# uNav44_r1_2.net
KiCad netlist of a schematic drawn in EAGLE
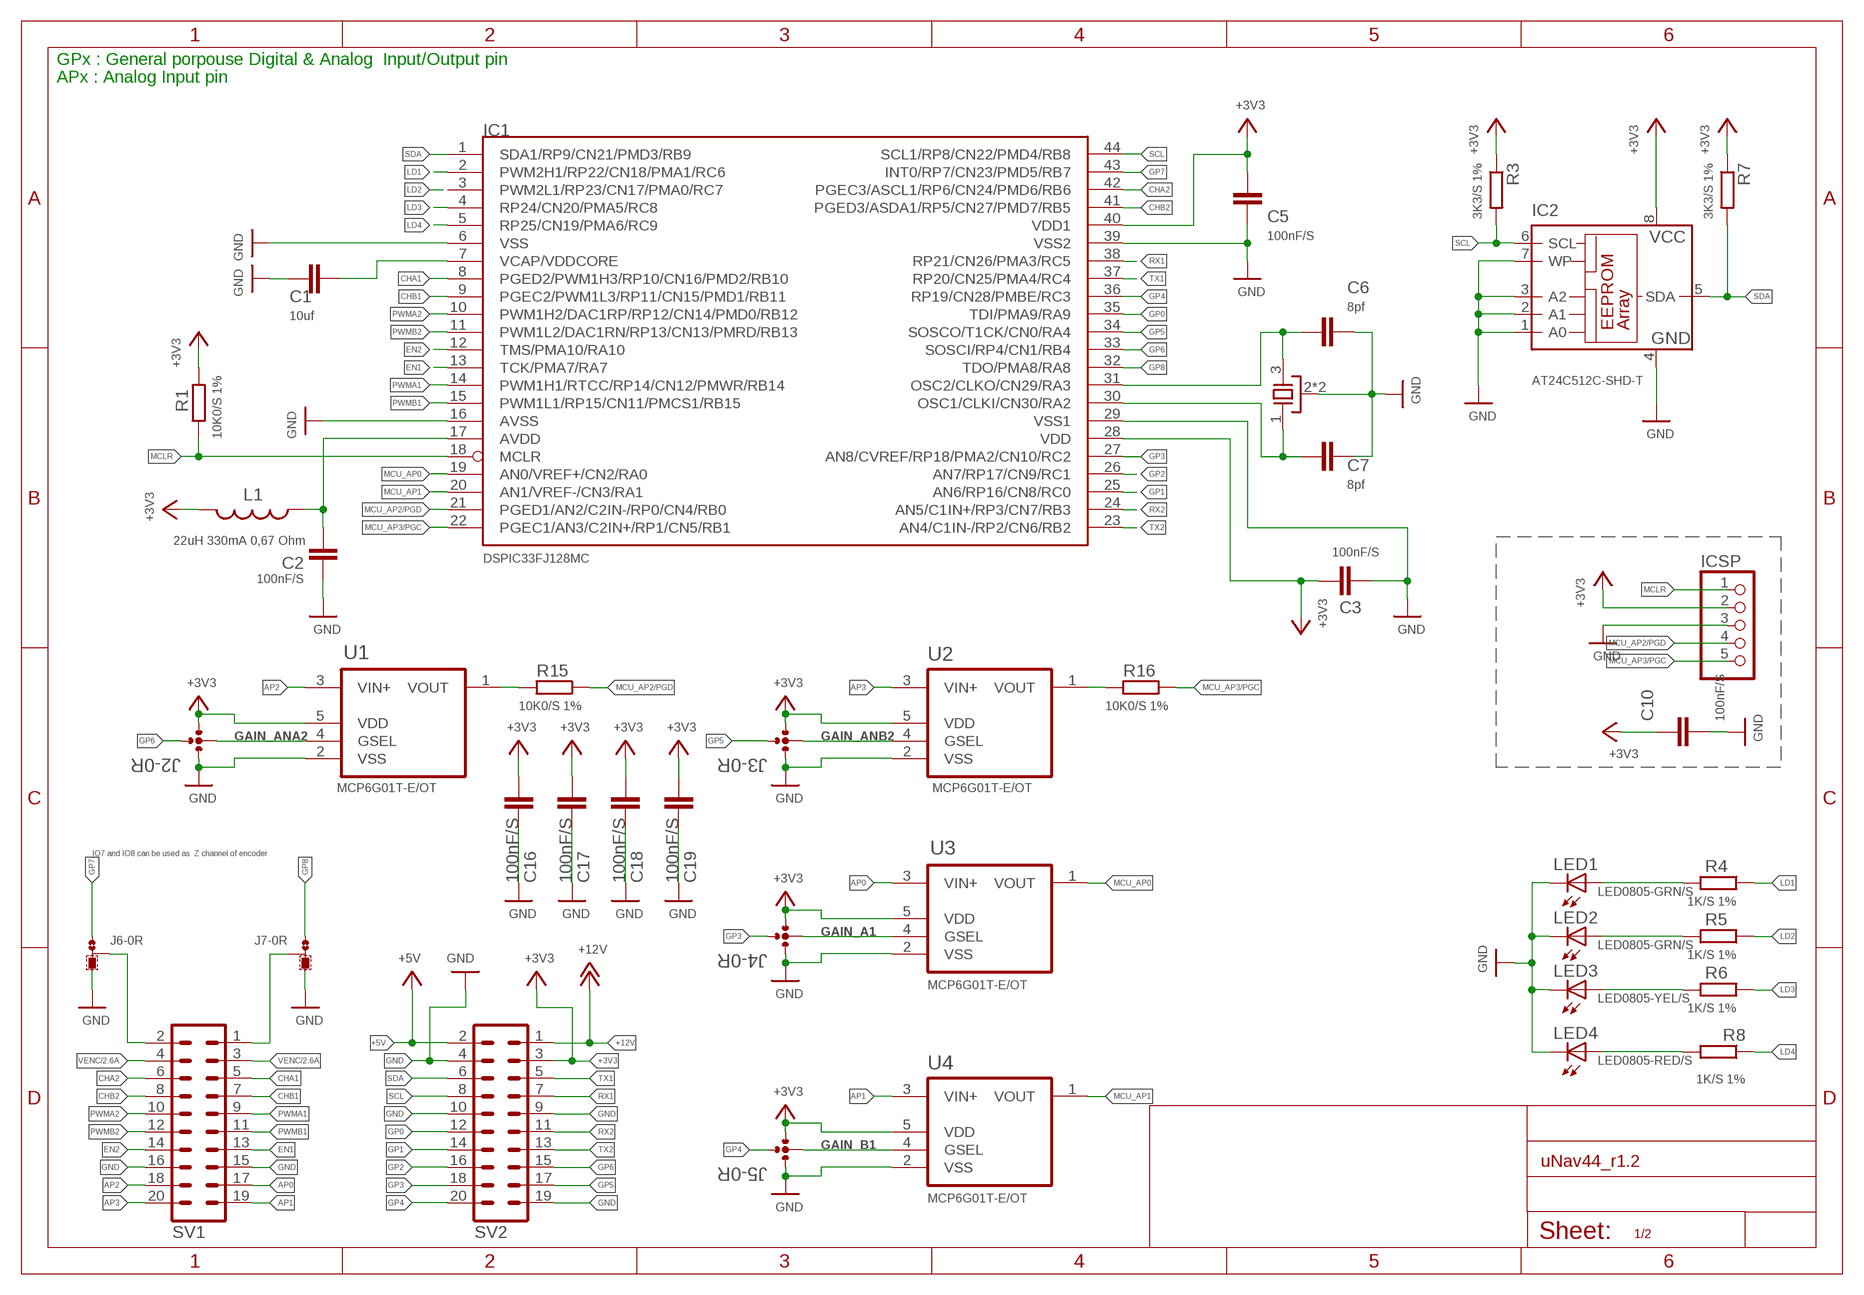
[diagram p0: schematic, sheet 1]
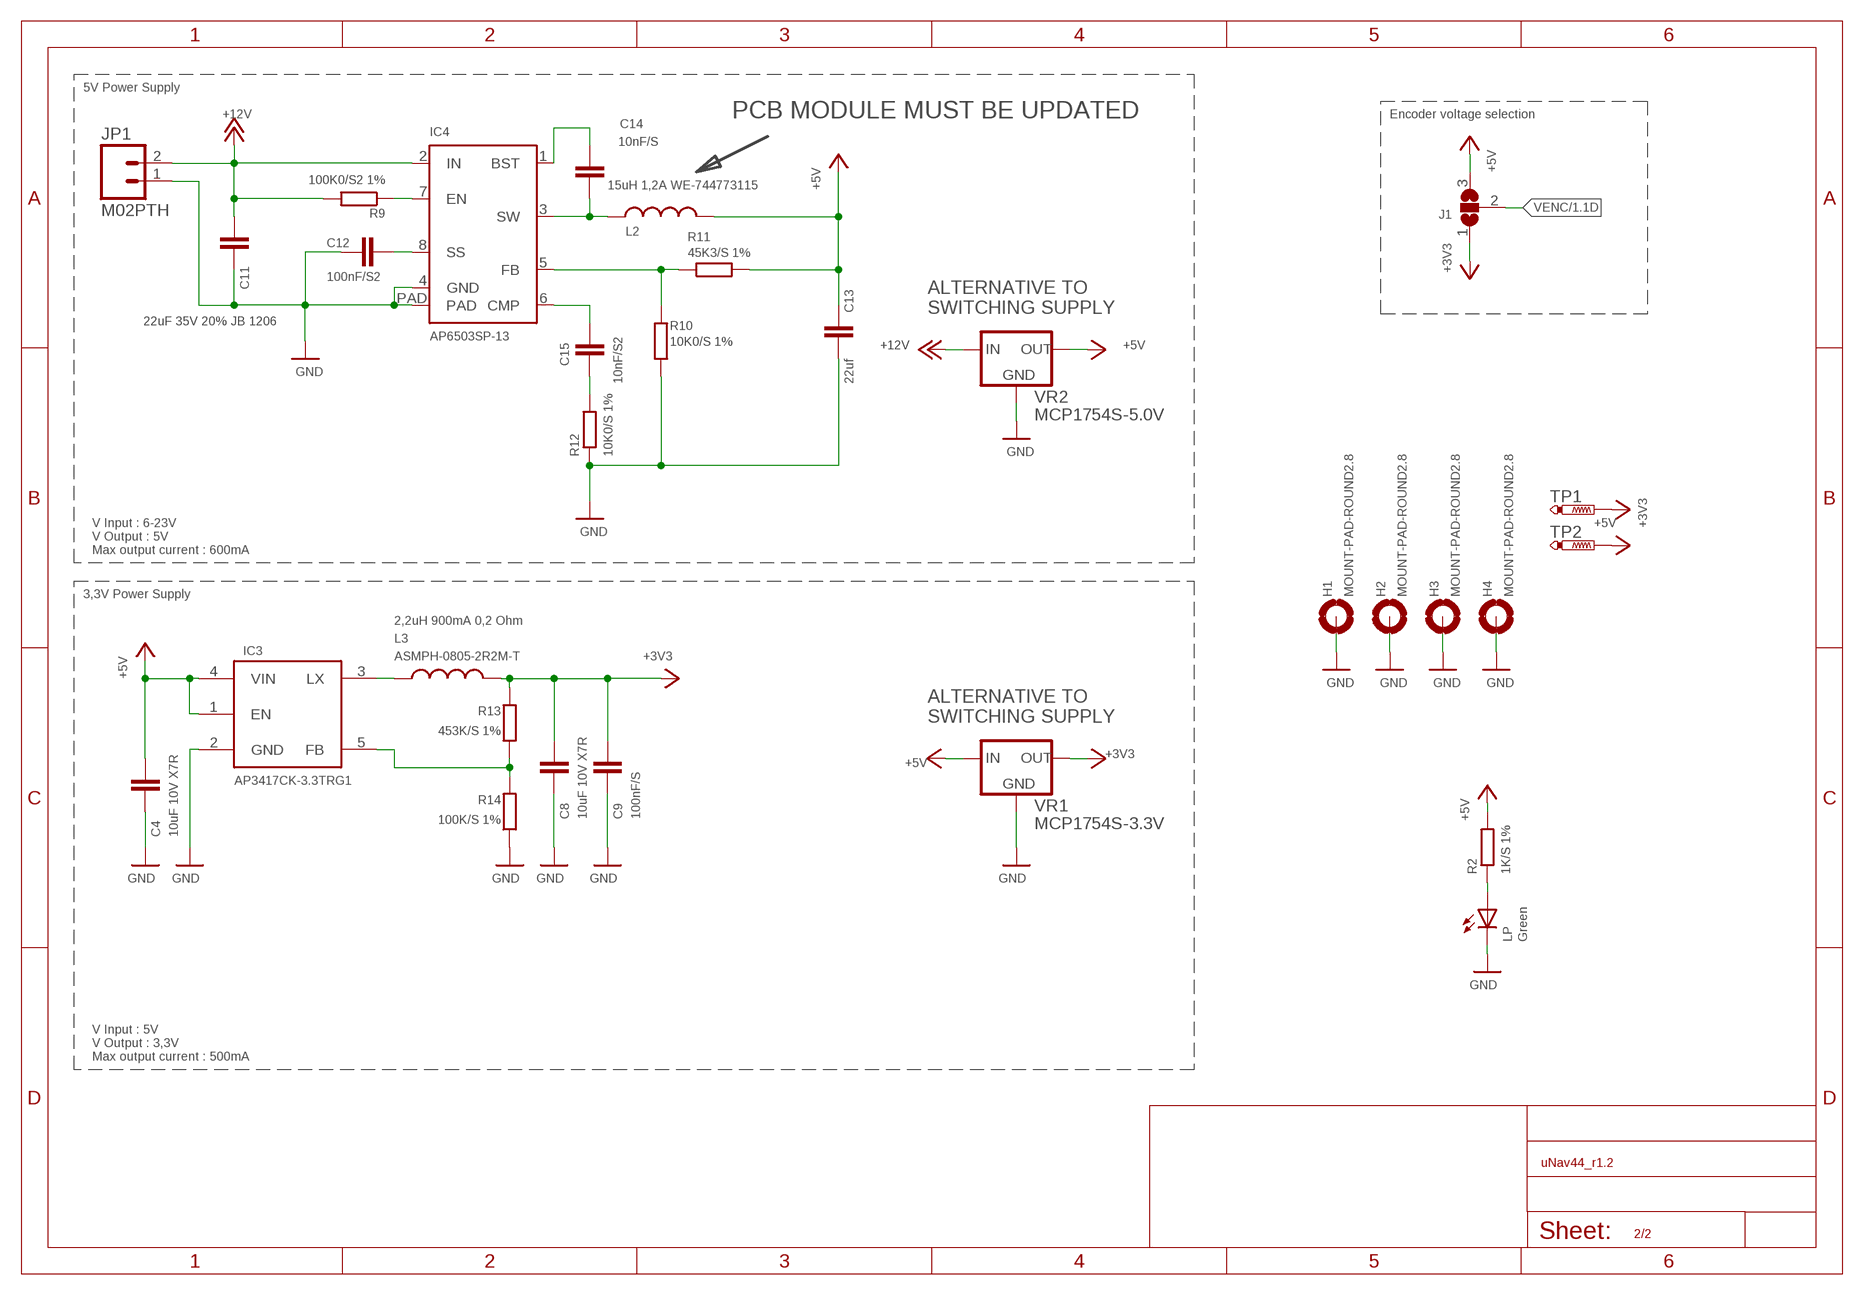
[diagram p1: schematic, sheet 2]

(export (version "E")
  (design (tool "Eeschema 10.0.6"))
  (components
    (comp (ref "C1")
      (value "10uf")
      (footprint "eagle-import:C1206")
      (libsource (lib "eagle-import") (part "C-EUC1206"))
    )
    (comp (ref "C2")
      (value "100nF/S")
      (footprint "eagle-import:C0603")
      (libsource (lib "eagle-import") (part "C-EUC0603"))
    )
    (comp (ref "C3")
      (value "100nF/S")
      (footprint "eagle-import:C0603")
      (libsource (lib "eagle-import") (part "C-EUC0603"))
    )
    (comp (ref "C5")
      (value "100nF/S")
      (footprint "eagle-import:C0603")
      (libsource (lib "eagle-import") (part "C-EUC0603"))
    )
    (comp (ref "C6")
      (value "8pf")
      (footprint "eagle-import:C0603")
      (libsource (lib "eagle-import") (part "C-EUC0603"))
    )
    (comp (ref "C7")
      (value "8pf")
      (footprint "eagle-import:C0603")
      (libsource (lib "eagle-import") (part "C-EUC0603"))
    )
    (comp (ref "C10")
      (value "100nF/S")
      (footprint "eagle-import:C0603")
      (libsource (lib "eagle-import") (part "C-EUC0603"))
    )
    (comp (ref "C16")
      (value "100nF/S")
      (footprint "eagle-import:C0603")
      (libsource (lib "eagle-import") (part "C-EUC0603"))
    )
    (comp (ref "C17")
      (value "100nF/S")
      (footprint "eagle-import:C0603")
      (libsource (lib "eagle-import") (part "C-EUC0603"))
    )
    (comp (ref "C18")
      (value "100nF/S")
      (footprint "eagle-import:C0603")
      (libsource (lib "eagle-import") (part "C-EUC0603"))
    )
    (comp (ref "C19")
      (value "100nF/S")
      (footprint "eagle-import:C0603")
      (libsource (lib "eagle-import") (part "C-EUC0603"))
    )
    (comp (ref "IC1")
      (value "DSPIC33FJ128MC")
      (footprint "eagle-import:TQFP44")
      (libsource (lib "eagle-import") (part "DSPIC33FJ128MC804-PT"))
    )
    (comp (ref "IC2")
      (value "AT24C512C-SHD-T")
      (footprint "eagle-import:SO-08M")
      (libsource (lib "eagle-import") (part "24SMAA01"))
    )
    (comp (ref "ICSP")
      (value "PINHD-1X05_2.54-S")
      (footprint "eagle-import:1X05-S")
      (libsource (lib "eagle-import") (part "PINHD-1X05_2.54-S"))
    )
    (comp (ref "J2")
      (value "0R-JUMP-4")
      (footprint "eagle-import:C0R-JUMP-4")
      (libsource (lib "eagle-import") (part "0R-JUMP-4"))
    )
    (comp (ref "J3")
      (value "0R-JUMP-4")
      (footprint "eagle-import:C0R-JUMP-4")
      (libsource (lib "eagle-import") (part "0R-JUMP-4"))
    )
    (comp (ref "J4")
      (value "0R-JUMP-4")
      (footprint "eagle-import:C0R-JUMP-4")
      (libsource (lib "eagle-import") (part "0R-JUMP-4"))
    )
    (comp (ref "J5")
      (value "0R-JUMP-4")
      (footprint "eagle-import:C0R-JUMP-4")
      (libsource (lib "eagle-import") (part "0R-JUMP-4"))
    )
    (comp (ref "J6")
      (value "0R-JUMPC")
      (footprint "eagle-import:C0R-JMP")
      (libsource (lib "eagle-import") (part "0R-JUMPC"))
    )
    (comp (ref "J7")
      (value "0R-JUMPC")
      (footprint "eagle-import:C0R-JMP")
      (libsource (lib "eagle-import") (part "0R-JUMPC"))
    )
    (comp (ref "L1")
      (value "22uH 330mA 0,67 Ohm")
      (footprint "eagle-import:0805")
      (libsource (lib "eagle-import") (part "INDUCTOR0805"))
    )
    (comp (ref "LED1")
      (value "LED0805-GRN/S")
      (footprint "eagle-import:CHIPLED_0805")
      (libsource (lib "eagle-import") (part "LEDCHIPLED_0805"))
    )
    (comp (ref "LED2")
      (value "LED0805-GRN/S")
      (footprint "eagle-import:CHIPLED_0805")
      (libsource (lib "eagle-import") (part "LEDCHIPLED_0805"))
    )
    (comp (ref "LED3")
      (value "LED0805-YEL/S")
      (footprint "eagle-import:CHIPLED_0805")
      (libsource (lib "eagle-import") (part "LEDCHIPLED_0805"))
    )
    (comp (ref "LED4")
      (value "LED0805-RED/S")
      (footprint "eagle-import:CHIPLED_0805")
      (libsource (lib "eagle-import") (part "LEDCHIPLED_0805"))
    )
    (comp (ref "R1")
      (value "10K0/S 1%")
      (footprint "eagle-import:R0603")
      (libsource (lib "eagle-import") (part "R-EU_R0603"))
    )
    (comp (ref "R3")
      (value "3K3/S 1%")
      (footprint "eagle-import:R0603")
      (libsource (lib "eagle-import") (part "R-EU_R0603"))
    )
    (comp (ref "R4")
      (value "1K/S 1%")
      (footprint "eagle-import:R0603")
      (libsource (lib "eagle-import") (part "R-EU_R0603"))
    )
    (comp (ref "R5")
      (value "1K/S 1%")
      (footprint "eagle-import:R0603")
      (libsource (lib "eagle-import") (part "R-EU_R0603"))
    )
    (comp (ref "R6")
      (value "1K/S 1%")
      (footprint "eagle-import:R0603")
      (libsource (lib "eagle-import") (part "R-EU_R0603"))
    )
    (comp (ref "R7")
      (value "3K3/S 1%")
      (footprint "eagle-import:R0603")
      (libsource (lib "eagle-import") (part "R-EU_R0603"))
    )
    (comp (ref "R8")
      (value "1K/S 1%")
      (footprint "eagle-import:R0603")
      (libsource (lib "eagle-import") (part "R-EU_R0603"))
    )
    (comp (ref "R15")
      (value "10K0/S 1%")
      (footprint "eagle-import:R0603")
      (libsource (lib "eagle-import") (part "R-EU_R0603"))
    )
    (comp (ref "R16")
      (value "10K0/S 1%")
      (footprint "eagle-import:R0603")
      (libsource (lib "eagle-import") (part "R-EU_R0603"))
    )
    (comp (ref "SV1")
      (value "MA10-2")
      (footprint "eagle-import:MA10-2")
      (fields (field (name "OC_FARNELL") "unknown") (field (name "OC_NEWARK") "unknown"))
      (libsource (lib "eagle-import") (part "MA10-2"))
    )
    (comp (ref "SV2")
      (value "MA10-2")
      (footprint "eagle-import:MA10-2")
      (libsource (lib "eagle-import") (part "MA10-2"))
    )
    (comp (ref "U1")
      (value "MCP6G01T-E/OT")
      (footprint "eagle-import:SOT95P300X145-5N")
      (libsource (lib "eagle-import") (part "MCP6G01T-E/OT"))
    )
    (comp (ref "U2")
      (value "MCP6G01T-E/OT")
      (footprint "eagle-import:SOT95P300X145-5N")
      (libsource (lib "eagle-import") (part "MCP6G01T-E/OT"))
    )
    (comp (ref "U3")
      (value "MCP6G01T-E/OT")
      (footprint "eagle-import:SOT95P300X145-5N")
      (libsource (lib "eagle-import") (part "MCP6G01T-E/OT"))
    )
    (comp (ref "U4")
      (value "MCP6G01T-E/OT")
      (footprint "eagle-import:SOT95P300X145-5N")
      (libsource (lib "eagle-import") (part "MCP6G01T-E/OT"))
    )
    (comp (ref "XT1")
      (value "10Mhz 8pf SMD 3,20x2,50")
      (footprint "eagle-import:CTS_32X25")
      (libsource (lib "eagle-import") (part "CTS_32X25_SMD"))
    )
    (comp (ref "C4")
      (value "10uF 10V X7R")
      (footprint "eagle-import:C0805")
      (libsource (lib "eagle-import") (part "C-EUC0805"))
    )
    (comp (ref "C8")
      (value "10uF 10V X7R")
      (footprint "eagle-import:C0805")
      (libsource (lib "eagle-import") (part "C-EUC0805"))
    )
    (comp (ref "C9")
      (value "100nF/S")
      (footprint "eagle-import:C0603")
      (libsource (lib "eagle-import") (part "C-EUC0603"))
    )
    (comp (ref "C11")
      (value "22uF 35V 20% JB 1206")
      (footprint "eagle-import:C1206")
      (libsource (lib "eagle-import") (part "C-EUC1206"))
    )
    (comp (ref "C12")
      (value "100nF/S2")
      (footprint "eagle-import:C0603")
      (libsource (lib "eagle-import") (part "C-EUC0603"))
    )
    (comp (ref "C13")
      (value "22uf")
      (footprint "eagle-import:C1206")
      (libsource (lib "eagle-import") (part "C-EUC1206"))
    )
    (comp (ref "C14")
      (value "10nF/S")
      (footprint "eagle-import:C0603")
      (libsource (lib "eagle-import") (part "C-EUC0603"))
    )
    (comp (ref "C15")
      (value "10nF/S2")
      (footprint "eagle-import:C0603")
      (libsource (lib "eagle-import") (part "C-EUC0603"))
    )
    (comp (ref "H1")
      (value "MOUNT-PAD-ROUND2.8")
      (footprint "eagle-import:2,8-PAD")
      (libsource (lib "eagle-import") (part "MOUNT-PAD-ROUND2.8"))
    )
    (comp (ref "H2")
      (value "MOUNT-PAD-ROUND2.8")
      (footprint "eagle-import:2,8-PAD")
      (libsource (lib "eagle-import") (part "MOUNT-PAD-ROUND2.8"))
    )
    (comp (ref "H3")
      (value "MOUNT-PAD-ROUND2.8")
      (footprint "eagle-import:2,8-PAD")
      (libsource (lib "eagle-import") (part "MOUNT-PAD-ROUND2.8"))
    )
    (comp (ref "H4")
      (value "MOUNT-PAD-ROUND2.8")
      (footprint "eagle-import:2,8-PAD")
      (libsource (lib "eagle-import") (part "MOUNT-PAD-ROUND2.8"))
    )
    (comp (ref "IC3")
      (value "AP3417CK-3.3TRG1")
      (footprint "eagle-import:SOT-23-5")
      (libsource (lib "eagle-import") (part "AP3417CSOT-23-5"))
    )
    (comp (ref "IC4")
      (value "AP6503SP-13")
      (footprint "eagle-import:SO-8EP")
      (libsource (lib "eagle-import") (part "AP6503SP-13'SO-8EP'"))
    )
    (comp (ref "J1")
      (value "SJ2W")
      (footprint "eagle-import:SJ_2")
      (libsource (lib "eagle-import") (part "SJ2W"))
    )
    (comp (ref "JP1")
      (value "M02PTH")
      (footprint "eagle-import:1X02")
      (libsource (lib "eagle-import") (part "M02PTH"))
    )
    (comp (ref "L2")
      (value "15uH 1,2A WE-744773115")
      (footprint "eagle-import:1210")
      (libsource (lib "eagle-import") (part "INDUCTOR1210"))
    )
    (comp (ref "L3")
      (value "ASMPH-0805-2R2M-T")
      (footprint "eagle-import:0805")
      (libsource (lib "eagle-import") (part "INDUCTOR0805"))
    )
    (comp (ref "LP")
      (value "Green")
      (footprint "eagle-import:CHIPLED_0805")
      (libsource (lib "eagle-import") (part "LEDCHIPLED_0805"))
    )
    (comp (ref "R2")
      (value "1K/S 1%")
      (footprint "eagle-import:R0603")
      (libsource (lib "eagle-import") (part "R-EU_R0603"))
    )
    (comp (ref "R9")
      (value "100K0/S2 1%")
      (footprint "eagle-import:R0603")
      (libsource (lib "eagle-import") (part "R-EU_R0603"))
    )
    (comp (ref "R10")
      (value "10K0/S 1%")
      (footprint "eagle-import:R0603")
      (libsource (lib "eagle-import") (part "R-EU_R0603"))
    )
    (comp (ref "R11")
      (value "45K3/S 1%")
      (footprint "eagle-import:R0603")
      (libsource (lib "eagle-import") (part "R-EU_R0603"))
    )
    (comp (ref "R12")
      (value "10K0/S 1%")
      (footprint "eagle-import:R0603")
      (libsource (lib "eagle-import") (part "R-EU_R0603"))
    )
    (comp (ref "R13")
      (value "453K/S 1%")
      (footprint "eagle-import:R0603")
      (libsource (lib "eagle-import") (part "R-EU_R0603"))
    )
    (comp (ref "R14")
      (value "100K/S 1%")
      (footprint "eagle-import:R0603")
      (libsource (lib "eagle-import") (part "R-EU_R0603"))
    )
    (comp (ref "TP1")
      (value "PTR1TP07R")
      (footprint "eagle-import:TP07R")
      (libsource (lib "eagle-import") (part "PTR1TP07R"))
    )
    (comp (ref "TP2")
      (value "PTR1TP07R")
      (footprint "eagle-import:TP07R")
      (libsource (lib "eagle-import") (part "PTR1TP07R"))
    )
    (comp (ref "VR1")
      (value "MCP1754S-3.3V")
      (footprint "eagle-import:SOT89")
      (libsource (lib "eagle-import") (part "MCP1754S"))
    )
    (comp (ref "VR2")
      (value "MCP1754S-5.0V")
      (footprint "eagle-import:SOT89")
      (libsource (lib "eagle-import") (part "MCP1754S"))
    )
  )
  (nets
    (net (code "1") (name "+3V3") (class "Default")
      (node (ref "C10") (pin "1") (pinfunction "1_1") (pintype "passive"))
      (node (ref "C16") (pin "1") (pinfunction "1_1") (pintype "passive"))
      (node (ref "C17") (pin "1") (pinfunction "1_1") (pintype "passive"))
      (node (ref "C18") (pin "1") (pinfunction "1_1") (pintype "passive"))
      (node (ref "C19") (pin "1") (pinfunction "1_1") (pintype "passive"))
      (node (ref "C3") (pin "1") (pinfunction "1_1") (pintype "passive"))
      (node (ref "C5") (pin "2") (pinfunction "2_2") (pintype "passive"))
      (node (ref "C8") (pin "1") (pinfunction "1_1") (pintype "passive"))
      (node (ref "C9") (pin "1") (pinfunction "1_1") (pintype "passive"))
      (node (ref "IC1") (pin "28") (pinfunction "VDD_28") (pintype "power_in"))
      (node (ref "IC1") (pin "40") (pinfunction "VDD1_40") (pintype "power_in"))
      (node (ref "IC2") (pin "8") (pinfunction "VCC_8") (pintype "power_in"))
      (node (ref "ICSP") (pin "2") (pinfunction "2_2") (pintype "passive"))
      (node (ref "J1") (pin "1") (pinfunction "1_1") (pintype "passive"))
      (node (ref "J2") (pin "1") (pinfunction "1_1") (pintype "passive"))
      (node (ref "J3") (pin "1") (pinfunction "1_1") (pintype "passive"))
      (node (ref "J4") (pin "1") (pinfunction "1_1") (pintype "passive"))
      (node (ref "J5") (pin "1") (pinfunction "1_1") (pintype "passive"))
      (node (ref "L1") (pin "2") (pinfunction "2_2") (pintype "passive"))
      (node (ref "L3") (pin "2") (pinfunction "2_2") (pintype "passive"))
      (node (ref "R1") (pin "2") (pinfunction "2_2") (pintype "passive"))
      (node (ref "R13") (pin "2") (pinfunction "2_2") (pintype "passive"))
      (node (ref "R3") (pin "1") (pinfunction "1_1") (pintype "passive"))
      (node (ref "R7") (pin "1") (pinfunction "1_1") (pintype "passive"))
      (node (ref "SV2") (pin "3") (pinfunction "3_3") (pintype "passive"))
      (node (ref "TP1") (pin "TP") (pinfunction "TP_TP") (pintype "input"))
      (node (ref "U1") (pin "5") (pinfunction "VDD_5") (pintype "power_in"))
      (node (ref "U2") (pin "5") (pinfunction "VDD_5") (pintype "power_in"))
      (node (ref "U3") (pin "5") (pinfunction "VDD_5") (pintype "power_in"))
      (node (ref "U4") (pin "5") (pinfunction "VDD_5") (pintype "power_in"))
      (node (ref "VR1") (pin "3") (pinfunction "OUT_3") (pintype "passive"))
    )
    (net (code "2") (name "+5V") (class "Default")
      (node (ref "C13") (pin "1") (pinfunction "1_1") (pintype "passive"))
      (node (ref "C4") (pin "1") (pinfunction "1_1") (pintype "passive"))
      (node (ref "IC3") (pin "1") (pinfunction "EN_1") (pintype "bidirectional"))
      (node (ref "IC3") (pin "4") (pinfunction "VIN_4") (pintype "bidirectional"))
      (node (ref "J1") (pin "3") (pinfunction "3_3") (pintype "passive"))
      (node (ref "L2") (pin "2") (pinfunction "2_2") (pintype "passive"))
      (node (ref "R11") (pin "2") (pinfunction "2_2") (pintype "passive"))
      (node (ref "R2") (pin "2") (pinfunction "2_2") (pintype "passive"))
      (node (ref "SV2") (pin "2") (pinfunction "2_2") (pintype "passive"))
      (node (ref "TP2") (pin "TP") (pinfunction "TP_TP") (pintype "input"))
      (node (ref "VR1") (pin "1") (pinfunction "IN_1") (pintype "input"))
      (node (ref "VR2") (pin "3") (pinfunction "OUT_3") (pintype "passive"))
    )
    (net (code "3") (name "+12V") (class "Default")
      (node (ref "C11") (pin "1") (pinfunction "1_1") (pintype "passive"))
      (node (ref "IC4") (pin "2") (pinfunction "IN_2") (pintype "power_in"))
      (node (ref "JP1") (pin "2") (pinfunction "2_2") (pintype "passive"))
      (node (ref "R9") (pin "2") (pinfunction "2_2") (pintype "passive"))
      (node (ref "SV2") (pin "1") (pinfunction "1_1") (pintype "passive"))
      (node (ref "VR2") (pin "1") (pinfunction "IN_1") (pintype "input"))
    )
    (net (code "4") (name "AP0") (class "Default")
      (node (ref "SV1") (pin "17") (pinfunction "17_17") (pintype "passive"))
      (node (ref "U3") (pin "3") (pinfunction "VIN+_3") (pintype "input"))
    )
    (net (code "5") (name "AP1") (class "Default")
      (node (ref "SV1") (pin "19") (pinfunction "19_19") (pintype "passive"))
      (node (ref "U4") (pin "3") (pinfunction "VIN+_3") (pintype "input"))
    )
    (net (code "6") (name "AP2") (class "Default")
      (node (ref "SV1") (pin "18") (pinfunction "18_18") (pintype "passive"))
      (node (ref "U1") (pin "3") (pinfunction "VIN+_3") (pintype "input"))
    )
    (net (code "7") (name "AP3") (class "Default")
      (node (ref "SV1") (pin "20") (pinfunction "20_20") (pintype "passive"))
      (node (ref "U2") (pin "3") (pinfunction "VIN+_3") (pintype "input"))
    )
    (net (code "8") (name "CHA1") (class "Default")
      (node (ref "IC1") (pin "8") (pinfunction "PGED2/PWM1H3/RP10/CN16/PMD2/RB10_8") (pintype "bidirectional"))
      (node (ref "SV1") (pin "5") (pinfunction "5_5") (pintype "passive"))
    )
    (net (code "9") (name "CHA2") (class "Default")
      (node (ref "IC1") (pin "42") (pinfunction "PGEC3/ASCL1/RP6/CN24/PMD6/RB6_42") (pintype "bidirectional"))
      (node (ref "SV1") (pin "6") (pinfunction "6_6") (pintype "passive"))
    )
    (net (code "10") (name "CHB1") (class "Default")
      (node (ref "IC1") (pin "9") (pinfunction "PGEC2/PWM1L3/RP11/CN15/PMD1/RB11_9") (pintype "bidirectional"))
      (node (ref "SV1") (pin "7") (pinfunction "7_7") (pintype "passive"))
    )
    (net (code "11") (name "CHB2") (class "Default")
      (node (ref "IC1") (pin "41") (pinfunction "PGED3/ASDA1/RP5/CN27/PMD7/RB5_41") (pintype "bidirectional"))
      (node (ref "SV1") (pin "8") (pinfunction "8_8") (pintype "passive"))
    )
    (net (code "12") (name "EN1") (class "Default")
      (node (ref "IC1") (pin "13") (pinfunction "TCK/PMA7/RA7_13") (pintype "bidirectional"))
      (node (ref "SV1") (pin "13") (pinfunction "13_13") (pintype "passive"))
    )
    (net (code "13") (name "EN2") (class "Default")
      (node (ref "IC1") (pin "12") (pinfunction "TMS/PMA10/RA10_12") (pintype "bidirectional"))
      (node (ref "SV1") (pin "14") (pinfunction "14_14") (pintype "passive"))
    )
    (net (code "14") (name "GAIN_A1") (class "Default")
      (node (ref "J4") (pin "2") (pinfunction "2_2") (pintype "passive"))
      (node (ref "U3") (pin "4") (pinfunction "GSEL_4") (pintype "input"))
    )
    (net (code "15") (name "GAIN_ANA2") (class "Default")
      (node (ref "J2") (pin "2") (pinfunction "2_2") (pintype "passive"))
      (node (ref "U1") (pin "4") (pinfunction "GSEL_4") (pintype "input"))
    )
    (net (code "16") (name "GAIN_ANB2") (class "Default")
      (node (ref "J3") (pin "2") (pinfunction "2_2") (pintype "passive"))
      (node (ref "U2") (pin "4") (pinfunction "GSEL_4") (pintype "input"))
    )
    (net (code "17") (name "GAIN_B1") (class "Default")
      (node (ref "J5") (pin "2") (pinfunction "2_2") (pintype "passive"))
      (node (ref "U4") (pin "4") (pinfunction "GSEL_4") (pintype "input"))
    )
    (net (code "18") (name "GND") (class "Default")
      (node (ref "C1") (pin "2") (pinfunction "2_2") (pintype "passive"))
      (node (ref "C10") (pin "2") (pinfunction "2_2") (pintype "passive"))
      (node (ref "C11") (pin "2") (pinfunction "2_2") (pintype "passive"))
      (node (ref "C12") (pin "2") (pinfunction "2_2") (pintype "passive"))
      (node (ref "C13") (pin "2") (pinfunction "2_2") (pintype "passive"))
      (node (ref "C16") (pin "2") (pinfunction "2_2") (pintype "passive"))
      (node (ref "C17") (pin "2") (pinfunction "2_2") (pintype "passive"))
      (node (ref "C18") (pin "2") (pinfunction "2_2") (pintype "passive"))
      (node (ref "C19") (pin "2") (pinfunction "2_2") (pintype "passive"))
      (node (ref "C2") (pin "1") (pinfunction "1_1") (pintype "passive"))
      (node (ref "C3") (pin "2") (pinfunction "2_2") (pintype "passive"))
      (node (ref "C4") (pin "2") (pinfunction "2_2") (pintype "passive"))
      (node (ref "C5") (pin "1") (pinfunction "1_1") (pintype "passive"))
      (node (ref "C6") (pin "2") (pinfunction "2_2") (pintype "passive"))
      (node (ref "C7") (pin "1") (pinfunction "1_1") (pintype "passive"))
      (node (ref "C8") (pin "2") (pinfunction "2_2") (pintype "passive"))
      (node (ref "C9") (pin "2") (pinfunction "2_2") (pintype "passive"))
      (node (ref "H1") (pin "B2,8") (pinfunction "MOUNT_B2,8") (pintype "passive"))
      (node (ref "H2") (pin "B2,8") (pinfunction "MOUNT_B2,8") (pintype "passive"))
      (node (ref "H3") (pin "B2,8") (pinfunction "MOUNT_B2,8") (pintype "passive"))
      (node (ref "H4") (pin "B2,8") (pinfunction "MOUNT_B2,8") (pintype "passive"))
      (node (ref "IC1") (pin "16") (pinfunction "AVSS_16") (pintype "power_in"))
      (node (ref "IC1") (pin "29") (pinfunction "VSS1_29") (pintype "power_in"))
      (node (ref "IC1") (pin "39") (pinfunction "VSS2_39") (pintype "power_in"))
      (node (ref "IC1") (pin "6") (pinfunction "VSS_6") (pintype "power_in"))
      (node (ref "IC2") (pin "1") (pinfunction "A0_1") (pintype "input"))
      (node (ref "IC2") (pin "2") (pinfunction "A1_2") (pintype "input"))
      (node (ref "IC2") (pin "3") (pinfunction "A2_3") (pintype "input"))
      (node (ref "IC2") (pin "4") (pinfunction "GND_4") (pintype "power_in"))
      (node (ref "IC2") (pin "7") (pinfunction "WP_7") (pintype "input"))
      (node (ref "IC3") (pin "2") (pinfunction "GND_2") (pintype "bidirectional"))
      (node (ref "IC4") (pin "4") (pinfunction "GND_4") (pintype "power_in"))
      (node (ref "IC4") (pin "PAD") (pinfunction "PAD_PAD") (pintype "power_in"))
      (node (ref "ICSP") (pin "3") (pinfunction "3_3") (pintype "passive"))
      (node (ref "J2") (pin "3") (pinfunction "3_3") (pintype "passive"))
      (node (ref "J3") (pin "3") (pinfunction "3_3") (pintype "passive"))
      (node (ref "J4") (pin "3") (pinfunction "3_3") (pintype "passive"))
      (node (ref "J5") (pin "3") (pinfunction "3_3") (pintype "passive"))
      (node (ref "J6") (pin "3") (pinfunction "3_3") (pintype "passive"))
      (node (ref "J7") (pin "3") (pinfunction "3_3") (pintype "passive"))
      (node (ref "JP1") (pin "1") (pinfunction "1_1") (pintype "passive"))
      (node (ref "LED1") (pin "C") (pinfunction "C_C") (pintype "passive"))
      (node (ref "LED2") (pin "C") (pinfunction "C_C") (pintype "passive"))
      (node (ref "LED3") (pin "C") (pinfunction "C_C") (pintype "passive"))
      (node (ref "LED4") (pin "C") (pinfunction "C_C") (pintype "passive"))
      (node (ref "LP") (pin "C") (pinfunction "C_C") (pintype "passive"))
      (node (ref "R10") (pin "2") (pinfunction "2_2") (pintype "passive"))
      (node (ref "R12") (pin "1") (pinfunction "1_1") (pintype "passive"))
      (node (ref "R14") (pin "1") (pinfunction "1_1") (pintype "passive"))
      (node (ref "SV1") (pin "15") (pinfunction "15_15") (pintype "passive"))
      (node (ref "SV1") (pin "16") (pinfunction "16_16") (pintype "passive"))
      (node (ref "SV2") (pin "10") (pinfunction "10_10") (pintype "passive"))
      (node (ref "SV2") (pin "19") (pinfunction "19_19") (pintype "passive"))
      (node (ref "SV2") (pin "4") (pinfunction "4_4") (pintype "passive"))
      (node (ref "SV2") (pin "9") (pinfunction "9_9") (pintype "passive"))
      (node (ref "U1") (pin "2") (pinfunction "VSS_2") (pintype "passive"))
      (node (ref "U2") (pin "2") (pinfunction "VSS_2") (pintype "passive"))
      (node (ref "U3") (pin "2") (pinfunction "VSS_2") (pintype "passive"))
      (node (ref "U4") (pin "2") (pinfunction "VSS_2") (pintype "passive"))
      (node (ref "VR1") (pin "2") (pinfunction "GND_2") (pintype "input"))
      (node (ref "VR1") (pin "4") (pinfunction "GND_4") (pintype "input"))
      (node (ref "VR2") (pin "2") (pinfunction "GND_2") (pintype "input"))
      (node (ref "VR2") (pin "4") (pinfunction "GND_4") (pintype "input"))
      (node (ref "XT1") (pin "2") (pinfunction "GND_2") (pintype "power_in"))
      (node (ref "XT1") (pin "4") (pinfunction "GND_4") (pintype "power_in"))
    )
    (net (code "19") (name "GP0") (class "Default")
      (node (ref "IC1") (pin "35") (pinfunction "TDI/PMA9/RA9_35") (pintype "bidirectional"))
      (node (ref "SV2") (pin "12") (pinfunction "12_12") (pintype "passive"))
    )
    (net (code "20") (name "GP1") (class "Default")
      (node (ref "IC1") (pin "25") (pinfunction "AN6/RP16/CN8/RC0_25") (pintype "bidirectional"))
      (node (ref "SV2") (pin "14") (pinfunction "14_14") (pintype "passive"))
    )
    (net (code "21") (name "GP2") (class "Default")
      (node (ref "IC1") (pin "26") (pinfunction "AN7/RP17/CN9/RC1_26") (pintype "bidirectional"))
      (node (ref "SV2") (pin "16") (pinfunction "16_16") (pintype "passive"))
    )
    (net (code "22") (name "GP3") (class "Default")
      (node (ref "IC1") (pin "27") (pinfunction "AN8/CVREF/RP18/PMA2/CN10/RC2_27") (pintype "bidirectional"))
      (node (ref "J4") (pin "4") (pinfunction "4_4") (pintype "passive"))
      (node (ref "SV2") (pin "18") (pinfunction "18_18") (pintype "passive"))
    )
    (net (code "23") (name "GP4") (class "Default")
      (node (ref "IC1") (pin "36") (pinfunction "RP19/CN28/PMBE/RC3_36") (pintype "bidirectional"))
      (node (ref "J5") (pin "4") (pinfunction "4_4") (pintype "passive"))
      (node (ref "SV2") (pin "20") (pinfunction "20_20") (pintype "passive"))
    )
    (net (code "24") (name "GP5") (class "Default")
      (node (ref "IC1") (pin "34") (pinfunction "SOSCO/T1CK/CN0/RA4_34") (pintype "bidirectional"))
      (node (ref "J3") (pin "4") (pinfunction "4_4") (pintype "passive"))
      (node (ref "SV2") (pin "17") (pinfunction "17_17") (pintype "passive"))
    )
    (net (code "25") (name "GP6") (class "Default")
      (node (ref "IC1") (pin "33") (pinfunction "SOSCI/RP4/CN1/RB4_33") (pintype "bidirectional"))
      (node (ref "J2") (pin "4") (pinfunction "4_4") (pintype "passive"))
      (node (ref "SV2") (pin "15") (pinfunction "15_15") (pintype "passive"))
    )
    (net (code "26") (name "GP7") (class "Default")
      (node (ref "IC1") (pin "43") (pinfunction "INT0/RP7/CN23/PMD5/RB7_43") (pintype "bidirectional"))
      (node (ref "J6") (pin "1") (pinfunction "1_1") (pintype "passive"))
    )
    (net (code "27") (name "GP8") (class "Default")
      (node (ref "IC1") (pin "32") (pinfunction "TDO/PMA8/RA8_32") (pintype "bidirectional"))
      (node (ref "J7") (pin "1") (pinfunction "1_1") (pintype "passive"))
    )
    (net (code "28") (name "LD1") (class "Default")
      (node (ref "IC1") (pin "2") (pinfunction "PWM2H1/RP22/CN18/PMA1/RC6_2") (pintype "bidirectional"))
      (node (ref "R4") (pin "1") (pinfunction "1_1") (pintype "passive"))
    )
    (net (code "29") (name "LD2") (class "Default")
      (node (ref "IC1") (pin "3") (pinfunction "PWM2L1/RP23/CN17/PMA0/RC7_3") (pintype "bidirectional"))
      (node (ref "R5") (pin "1") (pinfunction "1_1") (pintype "passive"))
    )
    (net (code "30") (name "LD3") (class "Default")
      (node (ref "IC1") (pin "4") (pinfunction "RP24/CN20/PMA5/RC8_4") (pintype "bidirectional"))
      (node (ref "R6") (pin "1") (pinfunction "1_1") (pintype "passive"))
    )
    (net (code "31") (name "LD4") (class "Default")
      (node (ref "IC1") (pin "5") (pinfunction "RP25/CN19/PMA6/RC9_5") (pintype "bidirectional"))
      (node (ref "R8") (pin "1") (pinfunction "1_1") (pintype "passive"))
    )
    (net (code "32") (name "MCLR") (class "Default")
      (node (ref "IC1") (pin "18") (pinfunction "MCLR_18") (pintype "input"))
      (node (ref "ICSP") (pin "1") (pinfunction "1_1") (pintype "passive"))
      (node (ref "R1") (pin "1") (pinfunction "1_1") (pintype "passive"))
    )
    (net (code "33") (name "MCU_AP0") (class "Default")
      (node (ref "IC1") (pin "19") (pinfunction "AN0/VREF+/CN2/RA0_19") (pintype "bidirectional"))
      (node (ref "U3") (pin "1") (pinfunction "VOUT_1") (pintype "output"))
    )
    (net (code "34") (name "MCU_AP1") (class "Default")
      (node (ref "IC1") (pin "20") (pinfunction "AN1/VREF-/CN3/RA1_20") (pintype "bidirectional"))
      (node (ref "U4") (pin "1") (pinfunction "VOUT_1") (pintype "output"))
    )
    (net (code "35") (name "MCU_AP2{slash}PGD") (class "Default")
      (node (ref "IC1") (pin "21") (pinfunction "PGED1/AN2/C2IN-/RP0/CN4/RB0_21") (pintype "bidirectional"))
      (node (ref "ICSP") (pin "4") (pinfunction "4_4") (pintype "passive"))
      (node (ref "R15") (pin "1") (pinfunction "1_1") (pintype "passive"))
    )
    (net (code "36") (name "MCU_AP3{slash}PGC") (class "Default")
      (node (ref "IC1") (pin "22") (pinfunction "PGEC1/AN3/C2IN+/RP1/CN5/RB1_22") (pintype "bidirectional"))
      (node (ref "ICSP") (pin "5") (pinfunction "5_5") (pintype "passive"))
      (node (ref "R16") (pin "1") (pinfunction "1_1") (pintype "passive"))
    )
    (net (code "37") (name "Net-(C15-Pad2)") (class "Default")
      (node (ref "C15") (pin "2") (pinfunction "2_2") (pintype "passive"))
      (node (ref "R12") (pin "2") (pinfunction "2_2") (pintype "passive"))
    )
    (net (code "38") (name "Net-(IC1-AVDD)") (class "Default")
      (node (ref "C2") (pin "2") (pinfunction "2_2") (pintype "passive"))
      (node (ref "IC1") (pin "17") (pinfunction "AVDD_17") (pintype "power_in"))
      (node (ref "L1") (pin "1") (pinfunction "1_1") (pintype "passive"))
    )
    (net (code "39") (name "Net-(IC1-OSC1{slash}CLKI{slash}CN30{slash}RA2)") (class "Default")
      (node (ref "C7") (pin "2") (pinfunction "2_2") (pintype "passive"))
      (node (ref "IC1") (pin "30") (pinfunction "OSC1/CLKI/CN30/RA2_30") (pintype "bidirectional"))
      (node (ref "XT1") (pin "1") (pinfunction "X1_1") (pintype "bidirectional"))
    )
    (net (code "40") (name "Net-(IC1-OSC2{slash}CLKO{slash}CN29{slash}RA3)") (class "Default")
      (node (ref "C6") (pin "1") (pinfunction "1_1") (pintype "passive"))
      (node (ref "IC1") (pin "31") (pinfunction "OSC2/CLKO/CN29/RA3_31") (pintype "bidirectional"))
      (node (ref "XT1") (pin "3") (pinfunction "X2_3") (pintype "bidirectional"))
    )
    (net (code "41") (name "Net-(IC1-VCAP{slash}VDDCORE)") (class "Default")
      (node (ref "C1") (pin "1") (pinfunction "1_1") (pintype "passive"))
      (node (ref "IC1") (pin "7") (pinfunction "VCAP/VDDCORE_7") (pintype "power_in"))
    )
    (net (code "42") (name "Net-(IC3-FB)") (class "Default")
      (node (ref "IC3") (pin "5") (pinfunction "FB_5") (pintype "bidirectional"))
      (node (ref "R13") (pin "1") (pinfunction "1_1") (pintype "passive"))
      (node (ref "R14") (pin "2") (pinfunction "2_2") (pintype "passive"))
    )
    (net (code "43") (name "Net-(IC3-LX)") (class "Default")
      (node (ref "IC3") (pin "3") (pinfunction "LX_3") (pintype "bidirectional"))
      (node (ref "L3") (pin "1") (pinfunction "1_1") (pintype "passive"))
    )
    (net (code "44") (name "Net-(IC4-BST)") (class "Default")
      (node (ref "C14") (pin "1") (pinfunction "1_1") (pintype "passive"))
      (node (ref "IC4") (pin "1") (pinfunction "BST_1") (pintype "bidirectional"))
    )
    (net (code "45") (name "Net-(IC4-CMP)") (class "Default")
      (node (ref "C15") (pin "1") (pinfunction "1_1") (pintype "passive"))
      (node (ref "IC4") (pin "6") (pinfunction "CMP_6") (pintype "bidirectional"))
    )
    (net (code "46") (name "Net-(IC4-EN)") (class "Default")
      (node (ref "IC4") (pin "7") (pinfunction "EN_7") (pintype "bidirectional"))
      (node (ref "R9") (pin "1") (pinfunction "1_1") (pintype "passive"))
    )
    (net (code "47") (name "Net-(IC4-FB)") (class "Default")
      (node (ref "IC4") (pin "5") (pinfunction "FB_5") (pintype "bidirectional"))
      (node (ref "R10") (pin "1") (pinfunction "1_1") (pintype "passive"))
      (node (ref "R11") (pin "1") (pinfunction "1_1") (pintype "passive"))
    )
    (net (code "48") (name "Net-(IC4-SS)") (class "Default")
      (node (ref "C12") (pin "1") (pinfunction "1_1") (pintype "passive"))
      (node (ref "IC4") (pin "8") (pinfunction "SS_8") (pintype "bidirectional"))
    )
    (net (code "49") (name "Net-(IC4-SW)") (class "Default")
      (node (ref "C14") (pin "2") (pinfunction "2_2") (pintype "passive"))
      (node (ref "IC4") (pin "3") (pinfunction "SW_3") (pintype "bidirectional"))
      (node (ref "L2") (pin "1") (pinfunction "1_1") (pintype "passive"))
    )
    (net (code "50") (name "Net-(J6-Pad2)") (class "Default")
      (node (ref "J6") (pin "2") (pinfunction "2_2") (pintype "passive"))
      (node (ref "SV1") (pin "2") (pinfunction "2_2") (pintype "passive"))
    )
    (net (code "51") (name "Net-(J7-Pad2)") (class "Default")
      (node (ref "J7") (pin "2") (pinfunction "2_2") (pintype "passive"))
      (node (ref "SV1") (pin "1") (pinfunction "1_1") (pintype "passive"))
    )
    (net (code "52") (name "Net-(LED1-PadA)") (class "Default")
      (node (ref "LED1") (pin "A") (pinfunction "A_A") (pintype "passive"))
      (node (ref "R4") (pin "2") (pinfunction "2_2") (pintype "passive"))
    )
    (net (code "53") (name "Net-(LED2-PadA)") (class "Default")
      (node (ref "LED2") (pin "A") (pinfunction "A_A") (pintype "passive"))
      (node (ref "R5") (pin "2") (pinfunction "2_2") (pintype "passive"))
    )
    (net (code "54") (name "Net-(LED3-PadA)") (class "Default")
      (node (ref "LED3") (pin "A") (pinfunction "A_A") (pintype "passive"))
      (node (ref "R6") (pin "2") (pinfunction "2_2") (pintype "passive"))
    )
    (net (code "55") (name "Net-(LED4-PadA)") (class "Default")
      (node (ref "LED4") (pin "A") (pinfunction "A_A") (pintype "passive"))
      (node (ref "R8") (pin "2") (pinfunction "2_2") (pintype "passive"))
    )
    (net (code "56") (name "Net-(LP-PadA)") (class "Default")
      (node (ref "LP") (pin "A") (pinfunction "A_A") (pintype "passive"))
      (node (ref "R2") (pin "1") (pinfunction "1_1") (pintype "passive"))
    )
    (net (code "57") (name "Net-(U1-VOUT)") (class "Default")
      (node (ref "R15") (pin "2") (pinfunction "2_2") (pintype "passive"))
      (node (ref "U1") (pin "1") (pinfunction "VOUT_1") (pintype "output"))
    )
    (net (code "58") (name "Net-(U2-VOUT)") (class "Default")
      (node (ref "R16") (pin "2") (pinfunction "2_2") (pintype "passive"))
      (node (ref "U2") (pin "1") (pinfunction "VOUT_1") (pintype "output"))
    )
    (net (code "59") (name "PWMA1") (class "Default")
      (node (ref "IC1") (pin "14") (pinfunction "PWM1H1/RTCC/RP14/CN12/PMWR/RB14_14") (pintype "bidirectional"))
      (node (ref "SV1") (pin "9") (pinfunction "9_9") (pintype "passive"))
    )
    (net (code "60") (name "PWMA2") (class "Default")
      (node (ref "IC1") (pin "10") (pinfunction "PWM1H2/DAC1RP/RP12/CN14/PMD0/RB12_10") (pintype "bidirectional"))
      (node (ref "SV1") (pin "10") (pinfunction "10_10") (pintype "passive"))
    )
    (net (code "61") (name "PWMB1") (class "Default")
      (node (ref "IC1") (pin "15") (pinfunction "PWM1L1/RP15/CN11/PMCS1/RB15_15") (pintype "bidirectional"))
      (node (ref "SV1") (pin "11") (pinfunction "11_11") (pintype "passive"))
    )
    (net (code "62") (name "PWMB2") (class "Default")
      (node (ref "IC1") (pin "11") (pinfunction "PWM1L2/DAC1RN/RP13/CN13/PMRD/RB13_11") (pintype "bidirectional"))
      (node (ref "SV1") (pin "12") (pinfunction "12_12") (pintype "passive"))
    )
    (net (code "63") (name "RX1") (class "Default")
      (node (ref "IC1") (pin "38") (pinfunction "RP21/CN26/PMA3/RC5_38") (pintype "bidirectional"))
      (node (ref "SV2") (pin "7") (pinfunction "7_7") (pintype "passive"))
    )
    (net (code "64") (name "RX2") (class "Default")
      (node (ref "IC1") (pin "24") (pinfunction "AN5/C1IN+/RP3/CN7/RB3_24") (pintype "bidirectional"))
      (node (ref "SV2") (pin "11") (pinfunction "11_11") (pintype "passive"))
    )
    (net (code "65") (name "SCL") (class "Default")
      (node (ref "IC1") (pin "44") (pinfunction "SCL1/RP8/CN22/PMD4/RB8_44") (pintype "bidirectional"))
      (node (ref "IC2") (pin "6") (pinfunction "SCL_6") (pintype "input"))
      (node (ref "R3") (pin "2") (pinfunction "2_2") (pintype "passive"))
      (node (ref "SV2") (pin "8") (pinfunction "8_8") (pintype "passive"))
    )
    (net (code "66") (name "SDA") (class "Default")
      (node (ref "IC1") (pin "1") (pinfunction "SDA1/RP9/CN21/PMD3/RB9_1") (pintype "bidirectional"))
      (node (ref "IC2") (pin "5") (pinfunction "SDA_5") (pintype "bidirectional"))
      (node (ref "R7") (pin "2") (pinfunction "2_2") (pintype "passive"))
      (node (ref "SV2") (pin "6") (pinfunction "6_6") (pintype "passive"))
    )
    (net (code "67") (name "TX1") (class "Default")
      (node (ref "IC1") (pin "37") (pinfunction "RP20/CN25/PMA4/RC4_37") (pintype "bidirectional"))
      (node (ref "SV2") (pin "5") (pinfunction "5_5") (pintype "passive"))
    )
    (net (code "68") (name "TX2") (class "Default")
      (node (ref "IC1") (pin "23") (pinfunction "AN4/C1IN-/RP2/CN6/RB2_23") (pintype "bidirectional"))
      (node (ref "SV2") (pin "13") (pinfunction "13_13") (pintype "passive"))
    )
    (net (code "69") (name "VENC") (class "Default")
      (node (ref "J1") (pin "2") (pinfunction "2_2") (pintype "passive"))
      (node (ref "SV1") (pin "3") (pinfunction "3_3") (pintype "passive"))
      (node (ref "SV1") (pin "4") (pinfunction "4_4") (pintype "passive"))
    )
  )
)
